# M_C_ext_main_ftdi.net
KiCad netlist of a schematic drawn in EAGLE
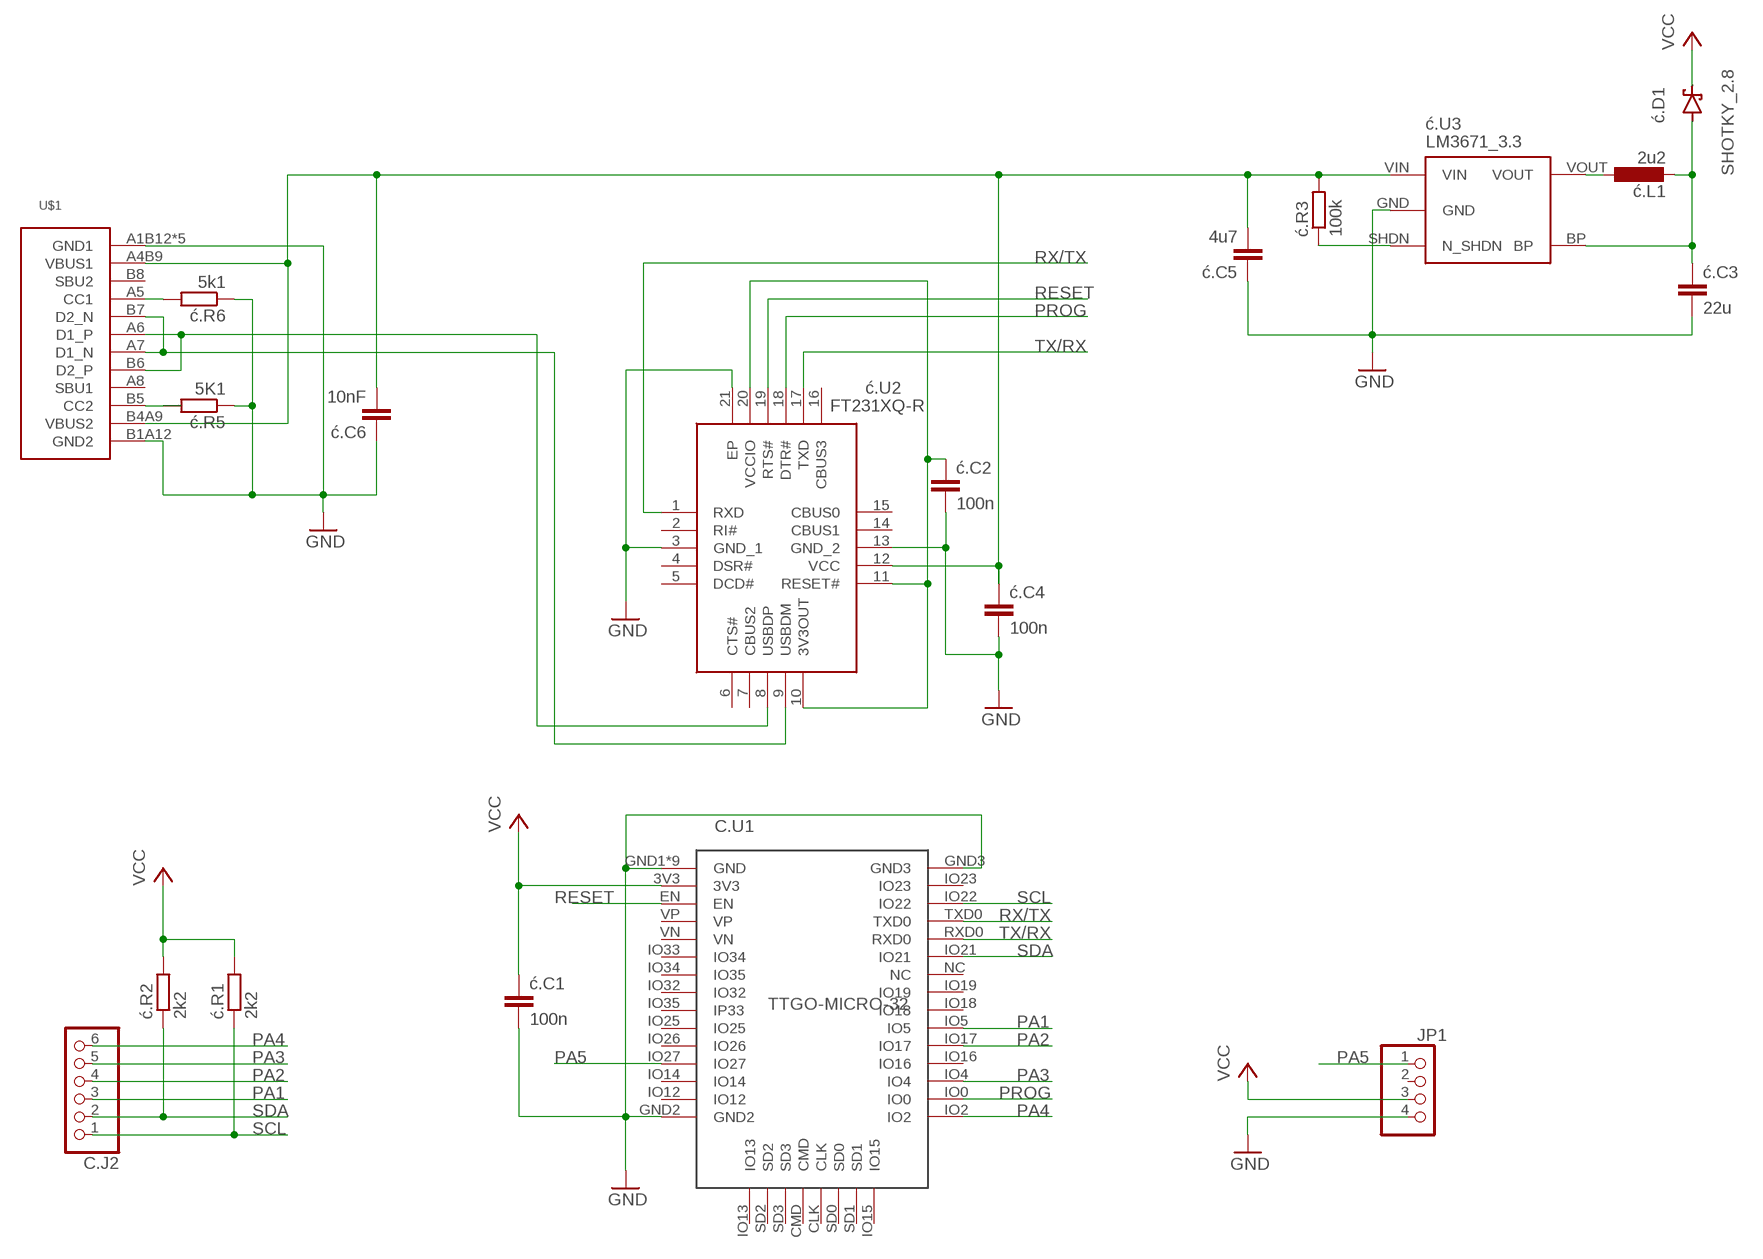
[diagram p0: schematic, sheet 1]

(export (version "E")
  (design (tool "Eeschema 10.0.6"))
  (components
    (comp (ref "C.J2")
      (value "PINHD-1X6")
      (footprint "eagle-import:1X06")
      (libsource (lib "eagle-import") (part "PINHD-1X6"))
    )
    (comp (ref "C.U1")
      (value "TTGO-MICRO-32")
      (footprint "eagle-import:TTGO-MICRO-32")
      (libsource (lib "eagle-import") (part "TTGO-MICRO-32"))
    )
    (comp (ref "JP1")
      (value "PINHD-1X4")
      (footprint "eagle-import:1X04")
      (libsource (lib "eagle-import") (part "PINHD-1X4"))
    )
    (comp (ref "U$1")
      (value "USB-C")
      (footprint "eagle-import:USB-C")
      (libsource (lib "eagle-import") (part "USB-C"))
    )
    (comp (ref "ć.C1")
      (value "100n")
      (footprint "eagle-import:C0603")
      (libsource (lib "eagle-import") (part "C-EUC0603"))
    )
    (comp (ref "ć.C2")
      (value "100n")
      (footprint "eagle-import:C0603")
      (libsource (lib "eagle-import") (part "C-EUC0603"))
    )
    (comp (ref "ć.C3")
      (value "22u")
      (footprint "eagle-import:C0805")
      (libsource (lib "eagle-import") (part "C-EUC0805"))
    )
    (comp (ref "ć.C4")
      (value "100n")
      (footprint "eagle-import:C0603")
      (libsource (lib "eagle-import") (part "C-EUC0603"))
    )
    (comp (ref "ć.C5")
      (value "4u7")
      (footprint "eagle-import:C0603")
      (libsource (lib "eagle-import") (part "C-EUC0603"))
    )
    (comp (ref "ć.C6")
      (value "10nF")
      (footprint "eagle-import:C0603")
      (libsource (lib "eagle-import") (part "C-EUC0603"))
    )
    (comp (ref "ć.D1")
      (value "SHOTKY_2.8")
      (footprint "eagle-import:SHOTKY_2.8")
      (libsource (lib "eagle-import") (part "SHOTKY_2.8"))
    )
    (comp (ref "ć.L1")
      (value "2u2")
      (footprint "eagle-import:L3230M")
      (libsource (lib "eagle-import") (part "L-EUL3230M"))
    )
    (comp (ref "ć.R1")
      (value "2k2")
      (footprint "eagle-import:R0603")
      (libsource (lib "eagle-import") (part "R-EU_R0603"))
    )
    (comp (ref "ć.R2")
      (value "2k2")
      (footprint "eagle-import:R0603")
      (libsource (lib "eagle-import") (part "R-EU_R0603"))
    )
    (comp (ref "ć.R3")
      (value "100k")
      (footprint "eagle-import:R0603")
      (libsource (lib "eagle-import") (part "R-EU_R0603"))
    )
    (comp (ref "ć.R5")
      (value "5K1")
      (footprint "eagle-import:R0603")
      (libsource (lib "eagle-import") (part "R-EU_R0603"))
    )
    (comp (ref "ć.R6")
      (value "5k1")
      (footprint "eagle-import:R0603")
      (libsource (lib "eagle-import") (part "R-EU_R0603"))
    )
    (comp (ref "ć.U2")
      (value "FT231XQ-R")
      (footprint "eagle-import:QFN50P400X400X80-21N")
      (libsource (lib "eagle-import") (part "FT231XQ-R"))
    )
    (comp (ref "ć.U3")
      (value "LM3671_3.3")
      (footprint "eagle-import:SOT32-5")
      (libsource (lib "eagle-import") (part "STABILISER_APE8865"))
    )
  )
  (nets
    (net (code "1") (name "/PA1") (class "Default")
      (node (ref "C.J2") (pin "3") (pinfunction "3_3") (pintype "passive"))
      (node (ref "C.U1") (pin "IO5") (pinfunction "IO5_IO5") (pintype "bidirectional"))
    )
    (net (code "2") (name "/PA2") (class "Default")
      (node (ref "C.J2") (pin "4") (pinfunction "4_4") (pintype "passive"))
      (node (ref "C.U1") (pin "IO17") (pinfunction "IO17_IO17") (pintype "bidirectional"))
    )
    (net (code "3") (name "/PA3") (class "Default")
      (node (ref "C.J2") (pin "5") (pinfunction "5_5") (pintype "passive"))
      (node (ref "C.U1") (pin "IO4") (pinfunction "IO4_IO4") (pintype "bidirectional"))
    )
    (net (code "4") (name "/PA4") (class "Default")
      (node (ref "C.J2") (pin "6") (pinfunction "6_6") (pintype "passive"))
      (node (ref "C.U1") (pin "IO2") (pinfunction "IO2_IO2") (pintype "bidirectional"))
    )
    (net (code "5") (name "/PA5") (class "Default")
      (node (ref "C.U1") (pin "IO27") (pinfunction "IO27_IO27") (pintype "bidirectional"))
      (node (ref "JP1") (pin "1") (pinfunction "1_1") (pintype "passive"))
    )
    (net (code "6") (name "/PROG") (class "Default")
      (node (ref "C.U1") (pin "IO0") (pinfunction "IO0_IO0") (pintype "bidirectional"))
      (node (ref "ć.U2") (pin "18") (pinfunction "DTR#_18") (pintype "bidirectional"))
    )
    (net (code "7") (name "/RESET") (class "Default")
      (node (ref "C.U1") (pin "EN") (pinfunction "EN_EN") (pintype "bidirectional"))
      (node (ref "ć.U2") (pin "19") (pinfunction "RTS#_19") (pintype "bidirectional"))
    )
    (net (code "8") (name "/RX{slash}TX") (class "Default")
      (node (ref "C.U1") (pin "TXD0") (pinfunction "TXD0_TXD0") (pintype "bidirectional"))
      (node (ref "ć.U2") (pin "1") (pinfunction "RXD_1") (pintype "bidirectional"))
    )
    (net (code "9") (name "/SCL") (class "Default")
      (node (ref "C.J2") (pin "1") (pinfunction "1_1") (pintype "passive"))
      (node (ref "C.U1") (pin "IO22") (pinfunction "IO22_IO22") (pintype "bidirectional"))
      (node (ref "ć.R1") (pin "1") (pinfunction "1_1") (pintype "passive"))
    )
    (net (code "10") (name "/SDA") (class "Default")
      (node (ref "C.J2") (pin "2") (pinfunction "2_2") (pintype "passive"))
      (node (ref "C.U1") (pin "IO21") (pinfunction "IO21_IO21") (pintype "bidirectional"))
      (node (ref "ć.R2") (pin "1") (pinfunction "1_1") (pintype "passive"))
    )
    (net (code "11") (name "/TX{slash}RX") (class "Default")
      (node (ref "C.U1") (pin "RXD0") (pinfunction "RXD0_RXD0") (pintype "bidirectional"))
      (node (ref "ć.U2") (pin "17") (pinfunction "TXD_17") (pintype "bidirectional"))
    )
    (net (code "12") (name "GND") (class "Default")
      (node (ref "C.U1") (pin "GND1") (pinfunction "GND_GND1") (pintype "power_in"))
      (node (ref "C.U1") (pin "GND10") (pinfunction "GND_GND10") (pintype "power_in"))
      (node (ref "C.U1") (pin "GND11") (pinfunction "GND_GND11") (pintype "power_in"))
      (node (ref "C.U1") (pin "GND2") (pinfunction "GND2_GND2") (pintype "power_in"))
      (node (ref "C.U1") (pin "GND3") (pinfunction "GND3_GND3") (pintype "power_in"))
      (node (ref "C.U1") (pin "GND4") (pinfunction "GND_GND4") (pintype "power_in"))
      (node (ref "C.U1") (pin "GND5") (pinfunction "GND_GND5") (pintype "power_in"))
      (node (ref "C.U1") (pin "GND6") (pinfunction "GND_GND6") (pintype "power_in"))
      (node (ref "C.U1") (pin "GND7") (pinfunction "GND_GND7") (pintype "power_in"))
      (node (ref "C.U1") (pin "GND8") (pinfunction "GND_GND8") (pintype "power_in"))
      (node (ref "C.U1") (pin "GND9") (pinfunction "GND_GND9") (pintype "power_in"))
      (node (ref "JP1") (pin "4") (pinfunction "4_4") (pintype "passive"))
      (node (ref "U$1") (pin "A1B12") (pinfunction "GND1_A1B12") (pintype "bidirectional"))
      (node (ref "U$1") (pin "B1A12") (pinfunction "GND2_B1A12") (pintype "bidirectional"))
      (node (ref "U$1") (pin "SH1") (pinfunction "GND1_SH1") (pintype "bidirectional"))
      (node (ref "U$1") (pin "SH2") (pinfunction "GND1_SH2") (pintype "bidirectional"))
      (node (ref "U$1") (pin "SH3") (pinfunction "GND1_SH3") (pintype "bidirectional"))
      (node (ref "U$1") (pin "SH4") (pinfunction "GND1_SH4") (pintype "bidirectional"))
      (node (ref "ć.C1") (pin "2") (pinfunction "2_2") (pintype "passive"))
      (node (ref "ć.C2") (pin "2") (pinfunction "2_2") (pintype "passive"))
      (node (ref "ć.C3") (pin "2") (pinfunction "2_2") (pintype "passive"))
      (node (ref "ć.C4") (pin "2") (pinfunction "2_2") (pintype "passive"))
      (node (ref "ć.C5") (pin "1") (pinfunction "1_1") (pintype "passive"))
      (node (ref "ć.C6") (pin "1") (pinfunction "1_1") (pintype "passive"))
      (node (ref "ć.R5") (pin "1") (pinfunction "1_1") (pintype "passive"))
      (node (ref "ć.R6") (pin "1") (pinfunction "1_1") (pintype "passive"))
      (node (ref "ć.U2") (pin "13") (pinfunction "GND_2_13") (pintype "bidirectional"))
      (node (ref "ć.U2") (pin "21") (pinfunction "EP_21") (pintype "bidirectional"))
      (node (ref "ć.U2") (pin "3") (pinfunction "GND_1_3") (pintype "bidirectional"))
      (node (ref "ć.U3") (pin "GND") (pinfunction "GND_GND") (pintype "bidirectional"))
    )
    (net (code "13") (name "Net-(U$1-CC1)") (class "Default")
      (node (ref "U$1") (pin "A5") (pinfunction "CC1_A5") (pintype "bidirectional"))
      (node (ref "ć.R6") (pin "2") (pinfunction "2_2") (pintype "passive"))
    )
    (net (code "14") (name "Net-(U$1-CC2)") (class "Default")
      (node (ref "U$1") (pin "B5") (pinfunction "CC2_B5") (pintype "bidirectional"))
      (node (ref "ć.R5") (pin "2") (pinfunction "2_2") (pintype "passive"))
    )
    (net (code "15") (name "Net-(U$1-D1_N)") (class "Default")
      (node (ref "U$1") (pin "A7") (pinfunction "D1_N_A7") (pintype "bidirectional"))
      (node (ref "U$1") (pin "B7") (pinfunction "D2_N_B7") (pintype "bidirectional"))
      (node (ref "ć.U2") (pin "9") (pinfunction "USBDM_9") (pintype "bidirectional"))
    )
    (net (code "16") (name "Net-(U$1-D1_P)") (class "Default")
      (node (ref "U$1") (pin "A6") (pinfunction "D1_P_A6") (pintype "bidirectional"))
      (node (ref "U$1") (pin "B6") (pinfunction "D2_P_B6") (pintype "bidirectional"))
      (node (ref "ć.U2") (pin "8") (pinfunction "USBDP_8") (pintype "bidirectional"))
    )
    (net (code "17") (name "Net-(U$1-VBUS1)") (class "Default")
      (node (ref "U$1") (pin "A4B9") (pinfunction "VBUS1_A4B9") (pintype "bidirectional"))
      (node (ref "U$1") (pin "B4A9") (pinfunction "VBUS2_B4A9") (pintype "bidirectional"))
      (node (ref "ć.C4") (pin "1") (pinfunction "1_1") (pintype "passive"))
      (node (ref "ć.C5") (pin "2") (pinfunction "2_2") (pintype "passive"))
      (node (ref "ć.C6") (pin "2") (pinfunction "2_2") (pintype "passive"))
      (node (ref "ć.R3") (pin "2") (pinfunction "2_2") (pintype "passive"))
      (node (ref "ć.U2") (pin "12") (pinfunction "VCC_12") (pintype "bidirectional"))
      (node (ref "ć.U3") (pin "VIN") (pinfunction "VIN_VIN") (pintype "bidirectional"))
    )
    (net (code "18") (name "Net-(ć.C3-Pad1)") (class "Default")
      (node (ref "ć.C3") (pin "1") (pinfunction "1_1") (pintype "passive"))
      (node (ref "ć.D1") (pin "A") (pinfunction "A_A") (pintype "passive"))
      (node (ref "ć.L1") (pin "2") (pinfunction "2_2") (pintype "passive"))
      (node (ref "ć.U3") (pin "BP") (pinfunction "BP_BP") (pintype "bidirectional"))
    )
    (net (code "19") (name "Net-(ć.L1-Pad1)") (class "Default")
      (node (ref "ć.L1") (pin "1") (pinfunction "1_1") (pintype "passive"))
      (node (ref "ć.U3") (pin "VOUT") (pinfunction "VOUT_VOUT") (pintype "bidirectional"))
    )
    (net (code "20") (name "Net-(ć.U2-3V3OUT)") (class "Default")
      (node (ref "ć.C2") (pin "1") (pinfunction "1_1") (pintype "passive"))
      (node (ref "ć.U2") (pin "10") (pinfunction "3V3OUT_10") (pintype "bidirectional"))
      (node (ref "ć.U2") (pin "11") (pinfunction "RESET#_11") (pintype "bidirectional"))
      (node (ref "ć.U2") (pin "20") (pinfunction "VCCIO_20") (pintype "bidirectional"))
    )
    (net (code "21") (name "Net-(ć.U3-N_SHDN)") (class "Default")
      (node (ref "ć.R3") (pin "1") (pinfunction "1_1") (pintype "passive"))
      (node (ref "ć.U3") (pin "SHDN") (pinfunction "N_SHDN_SHDN") (pintype "bidirectional"))
    )
    (net (code "22") (name "VCC") (class "Default")
      (node (ref "C.U1") (pin "3V3") (pinfunction "3V3_3V3") (pintype "power_in"))
      (node (ref "JP1") (pin "3") (pinfunction "3_3") (pintype "passive"))
      (node (ref "ć.C1") (pin "1") (pinfunction "1_1") (pintype "passive"))
      (node (ref "ć.D1") (pin "K") (pinfunction "C_K") (pintype "passive"))
      (node (ref "ć.R1") (pin "2") (pinfunction "2_2") (pintype "passive"))
      (node (ref "ć.R2") (pin "2") (pinfunction "2_2") (pintype "passive"))
    )
    (net (code "23") (name "unconnected-(C.U1-IO34-PadIO33)") (class "Default")
      (node (ref "C.U1") (pin "IO33") (pinfunction "IO34_IO33") (pintype "bidirectional"))
    )
    (net (code "24") (name "unconnected-(C.U1-IO35-PadIO34)") (class "Default")
      (node (ref "C.U1") (pin "IO34") (pinfunction "IO35_IO34") (pintype "bidirectional"))
    )
    (net (code "25") (name "unconnected-(C.U1-IP33-PadIO35)") (class "Default")
      (node (ref "C.U1") (pin "IO35") (pinfunction "IP33_IO35") (pintype "bidirectional"))
    )
    (net (code "26") (name "unconnected-(C.U1-PadCLK)") (class "Default")
      (node (ref "C.U1") (pin "CLK") (pinfunction "CLK_CLK") (pintype "bidirectional"))
    )
    (net (code "27") (name "unconnected-(C.U1-PadCMD)") (class "Default")
      (node (ref "C.U1") (pin "CMD") (pinfunction "CMD_CMD") (pintype "bidirectional"))
    )
    (net (code "28") (name "unconnected-(C.U1-PadIO12)") (class "Default")
      (node (ref "C.U1") (pin "IO12") (pinfunction "IO12_IO12") (pintype "bidirectional"))
    )
    (net (code "29") (name "unconnected-(C.U1-PadIO13)") (class "Default")
      (node (ref "C.U1") (pin "IO13") (pinfunction "IO13_IO13") (pintype "bidirectional"))
    )
    (net (code "30") (name "unconnected-(C.U1-PadIO14)") (class "Default")
      (node (ref "C.U1") (pin "IO14") (pinfunction "IO14_IO14") (pintype "bidirectional"))
    )
    (net (code "31") (name "unconnected-(C.U1-PadIO15)") (class "Default")
      (node (ref "C.U1") (pin "IO15") (pinfunction "IO15_IO15") (pintype "bidirectional"))
    )
    (net (code "32") (name "unconnected-(C.U1-PadIO16)") (class "Default")
      (node (ref "C.U1") (pin "IO16") (pinfunction "IO16_IO16") (pintype "bidirectional"))
    )
    (net (code "33") (name "unconnected-(C.U1-PadIO18)") (class "Default")
      (node (ref "C.U1") (pin "IO18") (pinfunction "IO18_IO18") (pintype "bidirectional"))
    )
    (net (code "34") (name "unconnected-(C.U1-PadIO19)") (class "Default")
      (node (ref "C.U1") (pin "IO19") (pinfunction "IO19_IO19") (pintype "bidirectional"))
    )
    (net (code "35") (name "unconnected-(C.U1-PadIO23)") (class "Default")
      (node (ref "C.U1") (pin "IO23") (pinfunction "IO23_IO23") (pintype "bidirectional"))
    )
    (net (code "36") (name "unconnected-(C.U1-PadIO25)") (class "Default")
      (node (ref "C.U1") (pin "IO25") (pinfunction "IO25_IO25") (pintype "bidirectional"))
    )
    (net (code "37") (name "unconnected-(C.U1-PadIO26)") (class "Default")
      (node (ref "C.U1") (pin "IO26") (pinfunction "IO26_IO26") (pintype "bidirectional"))
    )
    (net (code "38") (name "unconnected-(C.U1-PadIO32)") (class "Default")
      (node (ref "C.U1") (pin "IO32") (pinfunction "IO32_IO32") (pintype "bidirectional"))
    )
    (net (code "39") (name "unconnected-(C.U1-PadNC)") (class "Default")
      (node (ref "C.U1") (pin "NC") (pinfunction "NC_NC") (pintype "no_connect"))
    )
    (net (code "40") (name "unconnected-(C.U1-PadSD0)") (class "Default")
      (node (ref "C.U1") (pin "SD0") (pinfunction "SD0_SD0") (pintype "bidirectional"))
    )
    (net (code "41") (name "unconnected-(C.U1-PadSD1)") (class "Default")
      (node (ref "C.U1") (pin "SD1") (pinfunction "SD1_SD1") (pintype "bidirectional"))
    )
    (net (code "42") (name "unconnected-(C.U1-PadSD2)") (class "Default")
      (node (ref "C.U1") (pin "SD2") (pinfunction "SD2_SD2") (pintype "bidirectional"))
    )
    (net (code "43") (name "unconnected-(C.U1-PadSD3)") (class "Default")
      (node (ref "C.U1") (pin "SD3") (pinfunction "SD3_SD3") (pintype "bidirectional"))
    )
    (net (code "44") (name "unconnected-(C.U1-PadVN)") (class "Default")
      (node (ref "C.U1") (pin "VN") (pinfunction "VN_VN") (pintype "bidirectional"))
    )
    (net (code "45") (name "unconnected-(C.U1-PadVP)") (class "Default")
      (node (ref "C.U1") (pin "VP") (pinfunction "VP_VP") (pintype "bidirectional"))
    )
    (net (code "46") (name "unconnected-(JP1-Pad2)") (class "Default")
      (node (ref "JP1") (pin "2") (pinfunction "2_2") (pintype "passive"))
    )
    (net (code "47") (name "unconnected-(U$1-SBU1-PadA8)") (class "Default")
      (node (ref "U$1") (pin "A8") (pinfunction "SBU1_A8") (pintype "bidirectional"))
    )
    (net (code "48") (name "unconnected-(U$1-SBU2-PadB8)") (class "Default")
      (node (ref "U$1") (pin "B8") (pinfunction "SBU2_B8") (pintype "bidirectional"))
    )
    (net (code "49") (name "unconnected-(ć.U2-CBUS0-Pad15)") (class "Default")
      (node (ref "ć.U2") (pin "15") (pinfunction "CBUS0_15") (pintype "bidirectional"))
    )
    (net (code "50") (name "unconnected-(ć.U2-CBUS1-Pad14)") (class "Default")
      (node (ref "ć.U2") (pin "14") (pinfunction "CBUS1_14") (pintype "bidirectional"))
    )
    (net (code "51") (name "unconnected-(ć.U2-CBUS2-Pad7)") (class "Default")
      (node (ref "ć.U2") (pin "7") (pinfunction "CBUS2_7") (pintype "bidirectional"))
    )
    (net (code "52") (name "unconnected-(ć.U2-CBUS3-Pad16)") (class "Default")
      (node (ref "ć.U2") (pin "16") (pinfunction "CBUS3_16") (pintype "bidirectional"))
    )
    (net (code "53") (name "unconnected-(ć.U2-CTS#-Pad6)") (class "Default")
      (node (ref "ć.U2") (pin "6") (pinfunction "CTS#_6") (pintype "bidirectional"))
    )
    (net (code "54") (name "unconnected-(ć.U2-DCD#-Pad5)") (class "Default")
      (node (ref "ć.U2") (pin "5") (pinfunction "DCD#_5") (pintype "bidirectional"))
    )
    (net (code "55") (name "unconnected-(ć.U2-DSR#-Pad4)") (class "Default")
      (node (ref "ć.U2") (pin "4") (pinfunction "DSR#_4") (pintype "bidirectional"))
    )
    (net (code "56") (name "unconnected-(ć.U2-RI#-Pad2)") (class "Default")
      (node (ref "ć.U2") (pin "2") (pinfunction "RI#_2") (pintype "bidirectional"))
    )
  )
)
